# oven_redux.net
KiCad netlist of a schematic drawn in EAGLE
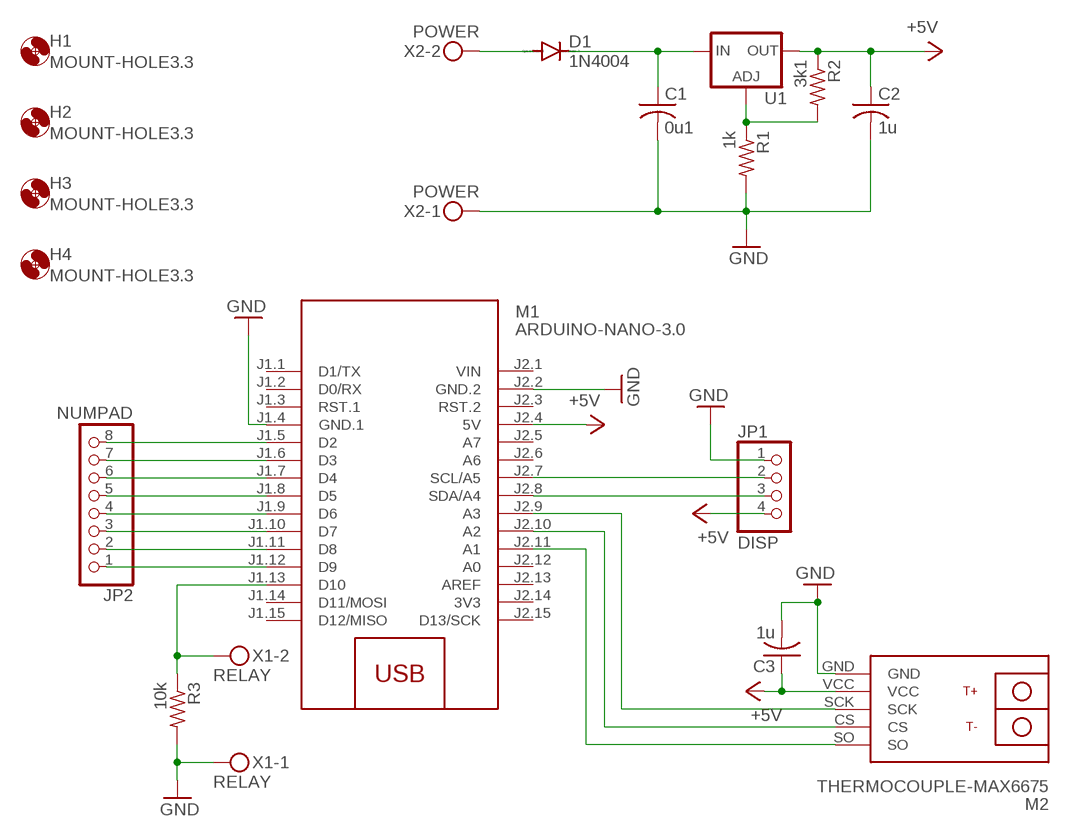
[diagram p0: schematic, sheet 1]

(export (version "E")
  (design (tool "Eeschema 10.0.6"))
  (components
    (comp (ref "C1")
      (value "0u1")
      (footprint "eagle-import:C025-050X050")
      (libsource (lib "eagle-import") (part "C-US025-050X050"))
    )
    (comp (ref "C2")
      (value "1u")
      (footprint "eagle-import:C025-050X050")
      (libsource (lib "eagle-import") (part "C-US025-050X050"))
    )
    (comp (ref "C3")
      (value "1u")
      (footprint "eagle-import:C025-050X050")
      (libsource (lib "eagle-import") (part "C-US025-050X050"))
    )
    (comp (ref "D1")
      (value "1N4004")
      (footprint "eagle-import:DO41-10")
      (libsource (lib "eagle-import") (part "1N4004"))
    )
    (comp (ref "H1")
      (value "MOUNT-HOLE3.3")
      (footprint "eagle-import:3,3")
      (libsource (lib "eagle-import") (part "MOUNT-HOLE3.3"))
    )
    (comp (ref "H2")
      (value "MOUNT-HOLE3.3")
      (footprint "eagle-import:3,3")
      (libsource (lib "eagle-import") (part "MOUNT-HOLE3.3"))
    )
    (comp (ref "H3")
      (value "MOUNT-HOLE3.3")
      (footprint "eagle-import:3,3")
      (libsource (lib "eagle-import") (part "MOUNT-HOLE3.3"))
    )
    (comp (ref "H4")
      (value "MOUNT-HOLE3.3")
      (footprint "eagle-import:3,3")
      (libsource (lib "eagle-import") (part "MOUNT-HOLE3.3"))
    )
    (comp (ref "JP1")
      (value "DISP")
      (footprint "eagle-import:1X04")
      (libsource (lib "eagle-import") (part "PINHD-1X4"))
    )
    (comp (ref "JP2")
      (value "NUMPAD")
      (footprint "eagle-import:1X08")
      (libsource (lib "eagle-import") (part "PINHD-1X8"))
    )
    (comp (ref "M1")
      (value "ARDUINO-NANO-3.0")
      (footprint "eagle-import:ARDUINO-NANO-3.0")
      (libsource (lib "eagle-import") (part "ARDUINO-NANO-3.0"))
    )
    (comp (ref "M2")
      (value "THERMOCOUPLE-MAX6675")
      (footprint "eagle-import:THERMOCOUPLE-MAX6675")
      (libsource (lib "eagle-import") (part "THERMOCOUPLE-MAX6675"))
    )
    (comp (ref "R1")
      (value "1k")
      (footprint "eagle-import:0204_7")
      (libsource (lib "eagle-import") (part "R-US_0204/7"))
    )
    (comp (ref "R2")
      (value "3k1")
      (footprint "eagle-import:0204_7")
      (libsource (lib "eagle-import") (part "R-US_0204/7"))
    )
    (comp (ref "R3")
      (value "10k")
      (footprint "eagle-import:0204_7")
      (libsource (lib "eagle-import") (part "R-US_0204/7"))
    )
    (comp (ref "U1")
      (value "LM317TL")
      (footprint "eagle-import:317TL")
      (libsource (lib "eagle-import") (part "LM317TL"))
    )
    (comp (ref "X1")
      (value "RELAY")
      (footprint "eagle-import:MKDSN1,5_2-5,08")
      (libsource (lib "eagle-import") (part "MKDSN1,5/2-5,08"))
    )
    (comp (ref "X2")
      (value "POWER")
      (footprint "eagle-import:MKDSN1,5_2-5,08")
      (libsource (lib "eagle-import") (part "MKDSN1,5/2-5,08"))
    )
  )
  (nets
    (net (code "1") (name "+5V") (class "Default")
      (node (ref "C2") (pin "1") (pinfunction "1_1") (pintype "passive"))
      (node (ref "C3") (pin "1") (pinfunction "1_1") (pintype "passive"))
      (node (ref "JP1") (pin "4") (pinfunction "4_4") (pintype "passive"))
      (node (ref "M1") (pin "J2.4") (pinfunction "5V_J2.4") (pintype "power_in"))
      (node (ref "M2") (pin "VCC") (pinfunction "VCC_VCC") (pintype "power_in"))
      (node (ref "R2") (pin "1") (pinfunction "1_1") (pintype "passive"))
      (node (ref "U1") (pin "2") (pinfunction "OUT_2") (pintype "passive"))
    )
    (net (code "2") (name "/3V3") (class "Default")
      (node (ref "M1") (pin "J2.14") (pinfunction "3V3_J2.14") (pintype "power_in"))
    )
    (net (code "3") (name "/VIN") (class "Default")
      (node (ref "M1") (pin "J2.1") (pinfunction "VIN_J2.1") (pintype "power_in"))
    )
    (net (code "4") (name "GND") (class "Default")
      (node (ref "C1") (pin "2") (pinfunction "2_2") (pintype "passive"))
      (node (ref "C2") (pin "2") (pinfunction "2_2") (pintype "passive"))
      (node (ref "C3") (pin "2") (pinfunction "2_2") (pintype "passive"))
      (node (ref "JP1") (pin "1") (pinfunction "1_1") (pintype "passive"))
      (node (ref "M1") (pin "J1.4") (pinfunction "GND.1_J1.4") (pintype "power_in"))
      (node (ref "M1") (pin "J2.2") (pinfunction "GND.2_J2.2") (pintype "power_in"))
      (node (ref "M2") (pin "GND") (pinfunction "GND_GND") (pintype "output"))
      (node (ref "R1") (pin "2") (pinfunction "2_2") (pintype "passive"))
      (node (ref "R3") (pin "2") (pinfunction "2_2") (pintype "passive"))
      (node (ref "X1") (pin "1") (pinfunction "KL_1") (pintype "passive"))
      (node (ref "X2") (pin "1") (pinfunction "KL_1") (pintype "passive"))
    )
    (net (code "5") (name "Net-(M1-A1)") (class "Default")
      (node (ref "M1") (pin "J2.11") (pinfunction "A1_J2.11") (pintype "bidirectional"))
      (node (ref "M2") (pin "SO") (pinfunction "SO_SO") (pintype "bidirectional"))
    )
    (net (code "6") (name "Net-(M1-A2)") (class "Default")
      (node (ref "M1") (pin "J2.10") (pinfunction "A2_J2.10") (pintype "bidirectional"))
      (node (ref "M2") (pin "CS") (pinfunction "CS_CS") (pintype "bidirectional"))
    )
    (net (code "7") (name "Net-(M1-A3)") (class "Default")
      (node (ref "M1") (pin "J2.9") (pinfunction "A3_J2.9") (pintype "bidirectional"))
      (node (ref "M2") (pin "SCK") (pinfunction "SCK_SCK") (pintype "bidirectional"))
    )
    (net (code "8") (name "Net-(M1-D2)") (class "Default")
      (node (ref "JP2") (pin "8") (pinfunction "8_8") (pintype "passive"))
      (node (ref "M1") (pin "J1.5") (pinfunction "D2_J1.5") (pintype "bidirectional"))
    )
    (net (code "9") (name "Net-(M1-D3)") (class "Default")
      (node (ref "JP2") (pin "7") (pinfunction "7_7") (pintype "passive"))
      (node (ref "M1") (pin "J1.6") (pinfunction "D3_J1.6") (pintype "bidirectional"))
    )
    (net (code "10") (name "Net-(M1-D4)") (class "Default")
      (node (ref "JP2") (pin "6") (pinfunction "6_6") (pintype "passive"))
      (node (ref "M1") (pin "J1.7") (pinfunction "D4_J1.7") (pintype "bidirectional"))
    )
    (net (code "11") (name "Net-(M1-D5)") (class "Default")
      (node (ref "JP2") (pin "5") (pinfunction "5_5") (pintype "passive"))
      (node (ref "M1") (pin "J1.8") (pinfunction "D5_J1.8") (pintype "bidirectional"))
    )
    (net (code "12") (name "Net-(M1-D6)") (class "Default")
      (node (ref "JP2") (pin "4") (pinfunction "4_4") (pintype "passive"))
      (node (ref "M1") (pin "J1.9") (pinfunction "D6_J1.9") (pintype "bidirectional"))
    )
    (net (code "13") (name "Net-(M1-D7)") (class "Default")
      (node (ref "JP2") (pin "3") (pinfunction "3_3") (pintype "passive"))
      (node (ref "M1") (pin "J1.10") (pinfunction "D7_J1.10") (pintype "bidirectional"))
    )
    (net (code "14") (name "Net-(M1-D8)") (class "Default")
      (node (ref "JP2") (pin "2") (pinfunction "2_2") (pintype "passive"))
      (node (ref "M1") (pin "J1.11") (pinfunction "D8_J1.11") (pintype "bidirectional"))
    )
    (net (code "15") (name "Net-(M1-D9)") (class "Default")
      (node (ref "JP2") (pin "1") (pinfunction "1_1") (pintype "passive"))
      (node (ref "M1") (pin "J1.12") (pinfunction "D9_J1.12") (pintype "bidirectional"))
    )
    (net (code "16") (name "Net-(M1-D10)") (class "Default")
      (node (ref "M1") (pin "J1.13") (pinfunction "D10_J1.13") (pintype "bidirectional"))
      (node (ref "R3") (pin "1") (pinfunction "1_1") (pintype "passive"))
      (node (ref "X1") (pin "2") (pinfunction "KL_2") (pintype "passive"))
    )
    (net (code "17") (name "Net-(M1-SCL{slash}A5)") (class "Default")
      (node (ref "JP1") (pin "2") (pinfunction "2_2") (pintype "passive"))
      (node (ref "M1") (pin "J2.7") (pinfunction "SCL/A5_J2.7") (pintype "bidirectional"))
    )
    (net (code "18") (name "Net-(M1-SDA{slash}A4)") (class "Default")
      (node (ref "JP1") (pin "3") (pinfunction "3_3") (pintype "passive"))
      (node (ref "M1") (pin "J2.8") (pinfunction "SDA/A4_J2.8") (pintype "bidirectional"))
    )
    (net (code "19") (name "Net-(U1-ADJ)") (class "Default")
      (node (ref "R1") (pin "1") (pinfunction "1_1") (pintype "passive"))
      (node (ref "R2") (pin "2") (pinfunction "2_2") (pintype "passive"))
      (node (ref "U1") (pin "1") (pinfunction "ADJ_1") (pintype "input"))
    )
    (net (code "20") (name "Net-(U1-IN)") (class "Default")
      (node (ref "C1") (pin "1") (pinfunction "1_1") (pintype "passive"))
      (node (ref "D1") (pin "C") (pinfunction "C_C") (pintype "passive"))
      (node (ref "U1") (pin "3") (pinfunction "IN_3") (pintype "input"))
    )
    (net (code "21") (name "Net-(X2B-KL)") (class "Default")
      (node (ref "D1") (pin "A") (pinfunction "A_A") (pintype "passive"))
      (node (ref "X2") (pin "2") (pinfunction "KL_2") (pintype "passive"))
    )
    (net (code "22") (name "unconnected-(M1-A0-PadJ2.12)") (class "Default")
      (node (ref "M1") (pin "J2.12") (pinfunction "A0_J2.12") (pintype "bidirectional"))
    )
    (net (code "23") (name "unconnected-(M1-A6-PadJ2.6)") (class "Default")
      (node (ref "M1") (pin "J2.6") (pinfunction "A6_J2.6") (pintype "bidirectional"))
    )
    (net (code "24") (name "unconnected-(M1-A7-PadJ2.5)") (class "Default")
      (node (ref "M1") (pin "J2.5") (pinfunction "A7_J2.5") (pintype "bidirectional"))
    )
    (net (code "25") (name "unconnected-(M1-AREF-PadJ2.13)") (class "Default")
      (node (ref "M1") (pin "J2.13") (pinfunction "AREF_J2.13") (pintype "bidirectional"))
    )
    (net (code "26") (name "unconnected-(M1-D0{slash}RX-PadJ1.2)") (class "Default")
      (node (ref "M1") (pin "J1.2") (pinfunction "D0/RX_J1.2") (pintype "bidirectional"))
    )
    (net (code "27") (name "unconnected-(M1-D1{slash}TX-PadJ1.1)") (class "Default")
      (node (ref "M1") (pin "J1.1") (pinfunction "D1/TX_J1.1") (pintype "bidirectional"))
    )
    (net (code "28") (name "unconnected-(M1-D11{slash}MOSI-PadJ1.14)") (class "Default")
      (node (ref "M1") (pin "J1.14") (pinfunction "D11/MOSI_J1.14") (pintype "bidirectional"))
    )
    (net (code "29") (name "unconnected-(M1-D12{slash}MISO-PadJ1.15)") (class "Default")
      (node (ref "M1") (pin "J1.15") (pinfunction "D12/MISO_J1.15") (pintype "bidirectional"))
    )
    (net (code "30") (name "unconnected-(M1-D13{slash}SCK-PadJ2.15)") (class "Default")
      (node (ref "M1") (pin "J2.15") (pinfunction "D13/SCK_J2.15") (pintype "bidirectional"))
    )
    (net (code "31") (name "unconnected-(M1-RST.1-PadJ1.3)") (class "Default")
      (node (ref "M1") (pin "J1.3") (pinfunction "RST.1_J1.3") (pintype "bidirectional"))
    )
    (net (code "32") (name "unconnected-(M1-RST.2-PadJ2.3)") (class "Default")
      (node (ref "M1") (pin "J2.3") (pinfunction "RST.2_J2.3") (pintype "bidirectional"))
    )
  )
)
